# Schema.net
KiCad netlist of a schematic drawn in EasyEDA
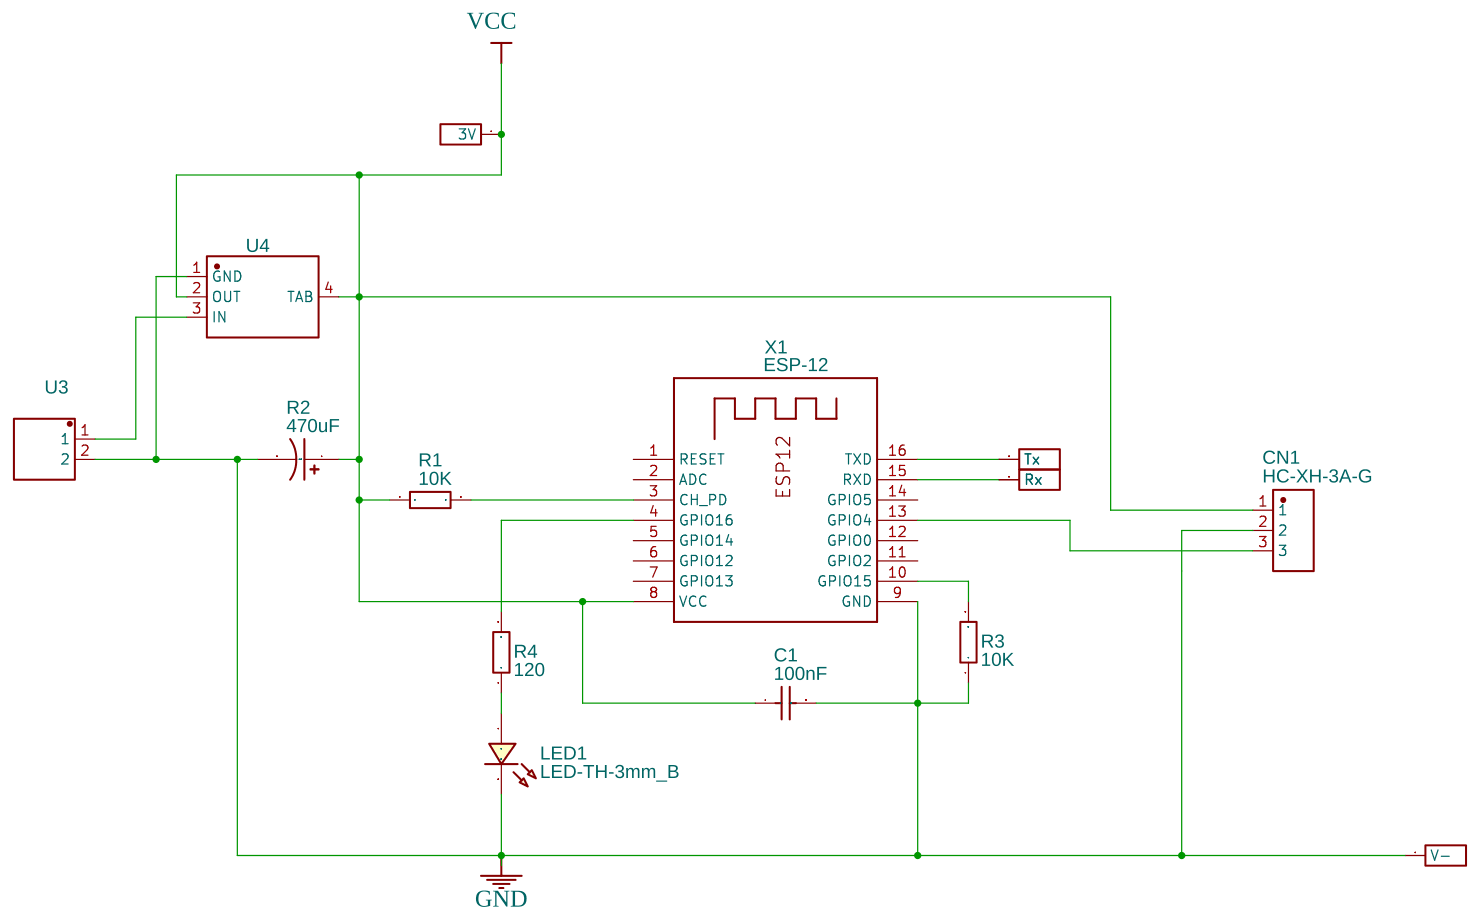
[diagram p0: schematic sheet]

(export (version "E")
  (design (tool "Eeschema 10.0.6"))
  (components
    (comp (ref "C1")
      (value "100nF")
      (fields (field (name "Manufacturer Part") "CL10B104JB8NNNC") (field (name "Manufacturer") "SAMSUNG"))
      (libsource (lib "") (part "CL10B104JB8NNNC"))
    )
    (comp (ref "CN1")
      (value "HC-XH-3A-G")
      (fields (field (name "Manufacturer") "HCTL(华灿天禄)"))
      (libsource (lib "") (part "HC-XH-3A-G"))
    )
    (comp (ref "J1") (value "HDR-M-2.54_1x1") (libsource (lib "") (part "HDR-M-2.54_1x1")))
    (comp (ref "J2") (value "HDR-M-2.54_1x1") (libsource (lib "") (part "HDR-M-2.54_1x1_2")))
    (comp (ref "J3") (value "HDR-M-2.54_1x1") (libsource (lib "") (part "HDR-M-2.54_1x1_3")))
    (comp (ref "J4") (value "HDR-M-2.54_1x1") (libsource (lib "") (part "HDR-M-2.54_1x1_1")))
    (comp (ref "LED1")
      (value "LED-TH-3mm_B")
      (fields
        (field (name "Manufacturer Part") "204-10SUBC/S400-A4")
        (field (name "Manufacturer") "EVERLIGHT(台湾亿光)")
      )
      (libsource (lib "") (part "LED-TH-3mm_B"))
    )
    (comp (ref "R1")
      (value "10K")
      (fields (field (name "Manufacturer Part") "RK73B1JTTD103J") (field (name "Manufacturer") "KOA"))
      (libsource (lib "") (part "RK73B1JTTD103J"))
    )
    (comp (ref "R2")
      (value "470uF")
      (fields
        (field (name "Manufacturer Part") "A700V106M12RATE040")
        (field (name "Manufacturer") "KEMET(基美)")
      )
      (libsource (lib "") (part "A700V106M12RATE040"))
    )
    (comp (ref "R3")
      (value "10K")
      (fields (field (name "Manufacturer Part") "RK73B1JTTD103J") (field (name "Manufacturer") "KOA"))
      (libsource (lib "") (part "RK73B1JTTD103J_1"))
    )
    (comp (ref "R4")
      (value "120")
      (fields (field (name "Manufacturer Part") "RK73B1JTTD103J") (field (name "Manufacturer") "KOA"))
      (libsource (lib "") (part "RK73B1JTTD103J_1"))
    )
    (comp (ref "U3")
      (value "S2B-PH-K-S(LF)(SN)")
      (fields (field (name "Manufacturer") "JST Sales America"))
      (libsource (lib "") (part "S2B-PH-K-S(LF)(SN)"))
    )
    (comp (ref "U4")
      (value "LT1117IST-2.85#TRPBF")
      (fields (field (name "Manufacturer") "Analog Devices"))
      (libsource (lib "") (part "LT1117IST-2.85#TRPBF"))
    )
    (comp (ref "X1") (value "ESP-12") (libsource (lib "") (part "ESP-12")))
  )
  (nets
    (net (code "1") (name "GND") (class "Default")
      (node (ref "C1") (pin "2") (pinfunction "2_2") (pintype "input"))
      (node (ref "CN1") (pin "2") (pinfunction "2_2") (pintype "unspecified"))
      (node (ref "J1") (pin "1") (pinfunction "V-_1") (pintype "input"))
      (node (ref "LED1") (pin "2") (pinfunction "2_2") (pintype "unspecified"))
      (node (ref "R2") (pin "2") (pinfunction "2_2") (pintype "unspecified"))
      (node (ref "R3") (pin "1") (pinfunction "1_1") (pintype "unspecified"))
      (node (ref "U3") (pin "2") (pinfunction "2_2") (pintype "unspecified"))
      (node (ref "U4") (pin "1") (pinfunction "GND_1") (pintype "unspecified"))
      (node (ref "X1") (pin "9") (pinfunction "GND_9") (pintype "passive"))
    )
    (net (code "2") (name "Net-(J3-Tx)") (class "Default")
      (node (ref "J3") (pin "1") (pinfunction "Tx_1") (pintype "input"))
      (node (ref "X1") (pin "16") (pinfunction "TXD_16") (pintype "output"))
    )
    (net (code "3") (name "Net-(J4-Rx)") (class "Default")
      (node (ref "J4") (pin "1") (pinfunction "Rx_1") (pintype "input"))
      (node (ref "X1") (pin "15") (pinfunction "RXD_15") (pintype "input"))
    )
    (net (code "4") (name "Net-(LED1-Pad1)") (class "Default")
      (node (ref "LED1") (pin "1") (pinfunction "1_1") (pintype "unspecified"))
      (node (ref "R4") (pin "1") (pinfunction "1_1") (pintype "unspecified"))
    )
    (net (code "5") (name "Net-(U4-IN)") (class "Default")
      (node (ref "U3") (pin "1") (pinfunction "1_1") (pintype "unspecified"))
      (node (ref "U4") (pin "3") (pinfunction "IN_3") (pintype "unspecified"))
    )
    (net (code "6") (name "Net-(X1-CH_PD)") (class "Default")
      (node (ref "R1") (pin "2") (pinfunction "2_2") (pintype "unspecified"))
      (node (ref "X1") (pin "3") (pinfunction "CH_PD_3") (pintype "input"))
    )
    (net (code "7") (name "Net-(X1-GPIO4)") (class "Default")
      (node (ref "CN1") (pin "3") (pinfunction "3_3") (pintype "unspecified"))
      (node (ref "X1") (pin "13") (pinfunction "GPIO4_13") (pintype "unspecified"))
    )
    (net (code "8") (name "Net-(X1-GPIO15)") (class "Default")
      (node (ref "R3") (pin "2") (pinfunction "2_2") (pintype "unspecified"))
      (node (ref "X1") (pin "10") (pinfunction "GPIO15_10") (pintype "unspecified"))
    )
    (net (code "9") (name "Net-(X1-GPIO16)") (class "Default")
      (node (ref "R4") (pin "2") (pinfunction "2_2") (pintype "unspecified"))
      (node (ref "X1") (pin "4") (pinfunction "GPIO16_4") (pintype "unspecified"))
    )
    (net (code "10") (name "VCC") (class "Default")
      (node (ref "C1") (pin "1") (pinfunction "1_1") (pintype "input"))
      (node (ref "CN1") (pin "1") (pinfunction "1_1") (pintype "unspecified"))
      (node (ref "J2") (pin "1") (pinfunction "3V_1") (pintype "input"))
      (node (ref "R1") (pin "1") (pinfunction "1_1") (pintype "unspecified"))
      (node (ref "R2") (pin "1") (pinfunction "1_1") (pintype "unspecified"))
      (node (ref "U4") (pin "2") (pinfunction "OUT_2") (pintype "unspecified"))
      (node (ref "U4") (pin "4") (pinfunction "TAB_4") (pintype "unspecified"))
      (node (ref "X1") (pin "8") (pinfunction "VCC_8") (pintype "passive"))
    )
    (net (code "11") (name "unconnected-(X1-ADC-Pad2)") (class "Default")
      (node (ref "X1") (pin "2") (pinfunction "ADC_2") (pintype "unspecified"))
    )
    (net (code "12") (name "unconnected-(X1-GPIO0-Pad12)") (class "Default")
      (node (ref "X1") (pin "12") (pinfunction "GPIO0_12") (pintype "unspecified"))
    )
    (net (code "13") (name "unconnected-(X1-GPIO2-Pad11)") (class "Default")
      (node (ref "X1") (pin "11") (pinfunction "GPIO2_11") (pintype "unspecified"))
    )
    (net (code "14") (name "unconnected-(X1-GPIO5-Pad14)") (class "Default")
      (node (ref "X1") (pin "14") (pinfunction "GPIO5_14") (pintype "unspecified"))
    )
    (net (code "15") (name "unconnected-(X1-GPIO12-Pad6)") (class "Default")
      (node (ref "X1") (pin "6") (pinfunction "GPIO12_6") (pintype "unspecified"))
    )
    (net (code "16") (name "unconnected-(X1-GPIO13-Pad7)") (class "Default")
      (node (ref "X1") (pin "7") (pinfunction "GPIO13_7") (pintype "unspecified"))
    )
    (net (code "17") (name "unconnected-(X1-GPIO14-Pad5)") (class "Default")
      (node (ref "X1") (pin "5") (pinfunction "GPIO14_5") (pintype "unspecified"))
    )
    (net (code "18") (name "unconnected-(X1-RESET-Pad1)") (class "Default")
      (node (ref "X1") (pin "1") (pinfunction "RESET_1") (pintype "input"))
    )
  )
)
